# tinyblink-rev3_2_1.net
KiCad netlist of a schematic drawn in EAGLE
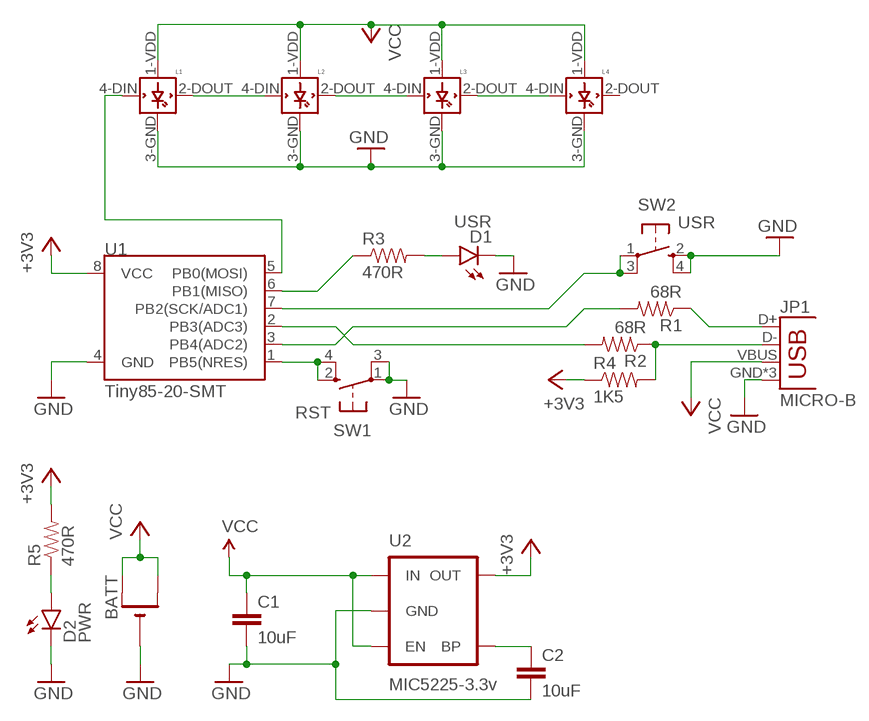
[diagram p0: schematic, sheet 1]

(export (version "E")
  (design (tool "Eeschema 10.0.6"))
  (components
    (comp (ref "BATT")
      (value "CR2032SMT")
      (footprint "eagle-import:CR2032-SMD")
      (libsource (lib "eagle-import") (part "CR2032SMT"))
    )
    (comp (ref "C1")
      (value "10uF")
      (footprint "eagle-import:0603-CAP")
      (libsource (lib "eagle-import") (part "CAP0603-CAP"))
    )
    (comp (ref "C2")
      (value "10uF")
      (footprint "eagle-import:0603-CAP")
      (libsource (lib "eagle-import") (part "CAP0603-CAP"))
    )
    (comp (ref "D1")
      (value "USR")
      (footprint "eagle-import:LED-0603")
      (libsource (lib "eagle-import") (part "LED-RED0603"))
    )
    (comp (ref "D2")
      (value "PWR")
      (footprint "eagle-import:LED-0603")
      (libsource (lib "eagle-import") (part "LED-GREEN0603"))
    )
    (comp (ref "JP1")
      (value "MICRO-B")
      (footprint "eagle-import:USB-MICROB")
      (libsource (lib "eagle-import") (part "USB-MICROB"))
    )
    (comp (ref "L1")
      (value "WS2812B")
      (footprint "eagle-import:WS2812B")
      (libsource (lib "eagle-import") (part "WS2812B"))
    )
    (comp (ref "L2")
      (value "WS2812B")
      (footprint "eagle-import:WS2812B")
      (libsource (lib "eagle-import") (part "WS2812B"))
    )
    (comp (ref "L3")
      (value "WS2812B")
      (footprint "eagle-import:WS2812B")
      (libsource (lib "eagle-import") (part "WS2812B"))
    )
    (comp (ref "L4")
      (value "WS2812B")
      (footprint "eagle-import:WS2812B")
      (libsource (lib "eagle-import") (part "WS2812B"))
    )
    (comp (ref "R1")
      (value "68R")
      (footprint "eagle-import:0603-RES")
      (libsource (lib "eagle-import") (part "RESISTOR0603-RES"))
    )
    (comp (ref "R2")
      (value "68R")
      (footprint "eagle-import:0603-RES")
      (libsource (lib "eagle-import") (part "RESISTOR0603-RES"))
    )
    (comp (ref "R3")
      (value "470R")
      (footprint "eagle-import:0603-RES")
      (libsource (lib "eagle-import") (part "RESISTOR0603-RES"))
    )
    (comp (ref "R4")
      (value "1K5")
      (footprint "eagle-import:0603-RES")
      (libsource (lib "eagle-import") (part "RESISTOR0603-RES"))
    )
    (comp (ref "R5")
      (value "470R")
      (footprint "eagle-import:0603-RES")
      (libsource (lib "eagle-import") (part "RESISTOR0603-RES"))
    )
    (comp (ref "SW1")
      (value "RST")
      (footprint "eagle-import:KMR2")
      (libsource (lib "eagle-import") (part "SPST_TACT-KMR2"))
    )
    (comp (ref "SW2")
      (value "USR")
      (footprint "eagle-import:KMR2")
      (libsource (lib "eagle-import") (part "SPST_TACT-KMR2"))
    )
    (comp (ref "U1")
      (value "Tiny85-20-SMT")
      (footprint "eagle-import:SO08-EIAJ")
      (libsource (lib "eagle-import") (part "ATTINY45TINY85-20-SMT"))
    )
    (comp (ref "U2")
      (value "MIC5225-3.3v")
      (footprint "eagle-import:SOT23-5")
      (libsource (lib "eagle-import") (part "MIC52053.3V"))
    )
  )
  (nets
    (net (code "1") (name "+3V3") (class "Default")
      (node (ref "R4") (pin "1") (pinfunction "1_1") (pintype "passive"))
      (node (ref "R5") (pin "2") (pinfunction "2_2") (pintype "passive"))
      (node (ref "U1") (pin "8") (pinfunction "VCC_8") (pintype "bidirectional"))
      (node (ref "U2") (pin "5") (pinfunction "OUT_5") (pintype "passive"))
    )
    (net (code "2") (name "GND") (class "Default")
      (node (ref "BATT") (pin "-") (pinfunction "-_-") (pintype "passive"))
      (node (ref "C1") (pin "2") (pinfunction "2_2") (pintype "passive"))
      (node (ref "C2") (pin "2") (pinfunction "2_2") (pintype "passive"))
      (node (ref "D1") (pin "C") (pinfunction "C_C") (pintype "passive"))
      (node (ref "D2") (pin "C") (pinfunction "C_C") (pintype "passive"))
      (node (ref "JP1") (pin "GND") (pinfunction "GND_GND") (pintype "bidirectional"))
      (node (ref "JP1") (pin "MT1") (pinfunction "GND_MT1") (pintype "bidirectional"))
      (node (ref "JP1") (pin "MT2") (pinfunction "GND_MT2") (pintype "bidirectional"))
      (node (ref "L1") (pin "3-GND") (pinfunction "GND_3-GND") (pintype "bidirectional"))
      (node (ref "L2") (pin "3-GND") (pinfunction "GND_3-GND") (pintype "bidirectional"))
      (node (ref "L3") (pin "3-GND") (pinfunction "GND_3-GND") (pintype "bidirectional"))
      (node (ref "L4") (pin "3-GND") (pinfunction "GND_3-GND") (pintype "bidirectional"))
      (node (ref "SW1") (pin "1") (pinfunction "P_1") (pintype "passive"))
      (node (ref "SW1") (pin "3") (pinfunction "P1_3") (pintype "passive"))
      (node (ref "SW2") (pin "2") (pinfunction "S_2") (pintype "passive"))
      (node (ref "SW2") (pin "4") (pinfunction "S1_4") (pintype "passive"))
      (node (ref "U1") (pin "4") (pinfunction "GND_4") (pintype "bidirectional"))
      (node (ref "U2") (pin "2") (pinfunction "GND_2") (pintype "input"))
    )
    (net (code "3") (name "Net-(D1-PadA)") (class "Default")
      (node (ref "D1") (pin "A") (pinfunction "A_A") (pintype "passive"))
      (node (ref "R3") (pin "2") (pinfunction "2_2") (pintype "passive"))
    )
    (net (code "4") (name "Net-(D2-PadA)") (class "Default")
      (node (ref "D2") (pin "A") (pinfunction "A_A") (pintype "passive"))
      (node (ref "R5") (pin "1") (pinfunction "1_1") (pintype "passive"))
    )
    (net (code "5") (name "Net-(JP1-PadD+)") (class "Default")
      (node (ref "JP1") (pin "D+") (pinfunction "D+_D+") (pintype "bidirectional"))
      (node (ref "R1") (pin "1") (pinfunction "1_1") (pintype "passive"))
    )
    (net (code "6") (name "Net-(JP1-PadD-)") (class "Default")
      (node (ref "JP1") (pin "D-") (pinfunction "D-_D-") (pintype "bidirectional"))
      (node (ref "R2") (pin "1") (pinfunction "1_1") (pintype "passive"))
      (node (ref "R4") (pin "2") (pinfunction "2_2") (pintype "passive"))
    )
    (net (code "7") (name "Net-(L1-DIN)") (class "Default")
      (node (ref "L1") (pin "4-DIN") (pinfunction "DIN_4-DIN") (pintype "input"))
      (node (ref "U1") (pin "5") (pinfunction "PB0(MOSI)_5") (pintype "bidirectional"))
    )
    (net (code "8") (name "Net-(L1-DOUT)") (class "Default")
      (node (ref "L1") (pin "2-DOUT") (pinfunction "DOUT_2-DOUT") (pintype "output"))
      (node (ref "L2") (pin "4-DIN") (pinfunction "DIN_4-DIN") (pintype "input"))
    )
    (net (code "9") (name "Net-(L2-DOUT)") (class "Default")
      (node (ref "L2") (pin "2-DOUT") (pinfunction "DOUT_2-DOUT") (pintype "output"))
      (node (ref "L3") (pin "4-DIN") (pinfunction "DIN_4-DIN") (pintype "input"))
    )
    (net (code "10") (name "Net-(L3-DOUT)") (class "Default")
      (node (ref "L3") (pin "2-DOUT") (pinfunction "DOUT_2-DOUT") (pintype "output"))
      (node (ref "L4") (pin "4-DIN") (pinfunction "DIN_4-DIN") (pintype "input"))
    )
    (net (code "11") (name "Net-(SW1-S)") (class "Default")
      (node (ref "SW1") (pin "2") (pinfunction "S_2") (pintype "passive"))
      (node (ref "SW1") (pin "4") (pinfunction "S1_4") (pintype "passive"))
      (node (ref "U1") (pin "1") (pinfunction "PB5(NRES)_1") (pintype "bidirectional"))
    )
    (net (code "12") (name "Net-(SW2-P)") (class "Default")
      (node (ref "SW2") (pin "1") (pinfunction "P_1") (pintype "passive"))
      (node (ref "SW2") (pin "3") (pinfunction "P1_3") (pintype "passive"))
      (node (ref "U1") (pin "7") (pinfunction "PB2(SCK/ADC1)_7") (pintype "bidirectional"))
    )
    (net (code "13") (name "Net-(U1-PB1(MISO))") (class "Default")
      (node (ref "R3") (pin "1") (pinfunction "1_1") (pintype "passive"))
      (node (ref "U1") (pin "6") (pinfunction "PB1(MISO)_6") (pintype "bidirectional"))
    )
    (net (code "14") (name "Net-(U1-PB3(ADC3))") (class "Default")
      (node (ref "R2") (pin "2") (pinfunction "2_2") (pintype "passive"))
      (node (ref "U1") (pin "2") (pinfunction "PB3(ADC3)_2") (pintype "bidirectional"))
    )
    (net (code "15") (name "Net-(U1-PB4(ADC2))") (class "Default")
      (node (ref "R1") (pin "2") (pinfunction "2_2") (pintype "passive"))
      (node (ref "U1") (pin "3") (pinfunction "PB4(ADC2)_3") (pintype "bidirectional"))
    )
    (net (code "16") (name "Net-(U2-BP)") (class "Default")
      (node (ref "C2") (pin "1") (pinfunction "1_1") (pintype "passive"))
      (node (ref "U2") (pin "4") (pinfunction "BP_4") (pintype "input"))
    )
    (net (code "17") (name "VCC") (class "Default")
      (node (ref "BATT") (pin "+$1") (pinfunction "+_+$1") (pintype "passive"))
      (node (ref "BATT") (pin "+$2") (pinfunction "+1_+$2") (pintype "passive"))
      (node (ref "C1") (pin "1") (pinfunction "1_1") (pintype "passive"))
      (node (ref "JP1") (pin "VBUS") (pinfunction "VBUS_VBUS") (pintype "bidirectional"))
      (node (ref "L1") (pin "1-VDD") (pinfunction "VDD_1-VDD") (pintype "bidirectional"))
      (node (ref "L2") (pin "1-VDD") (pinfunction "VDD_1-VDD") (pintype "bidirectional"))
      (node (ref "L3") (pin "1-VDD") (pinfunction "VDD_1-VDD") (pintype "bidirectional"))
      (node (ref "L4") (pin "1-VDD") (pinfunction "VDD_1-VDD") (pintype "bidirectional"))
      (node (ref "U2") (pin "1") (pinfunction "IN_1") (pintype "input"))
      (node (ref "U2") (pin "3") (pinfunction "EN_3") (pintype "input"))
    )
    (net (code "18") (name "unconnected-(L4-DOUT-Pad2-DOUT)") (class "Default")
      (node (ref "L4") (pin "2-DOUT") (pinfunction "DOUT_2-DOUT") (pintype "output"))
    )
  )
)
